# 12_WIFI_Module.net
KiCad netlist of a schematic drawn in Altium Designer
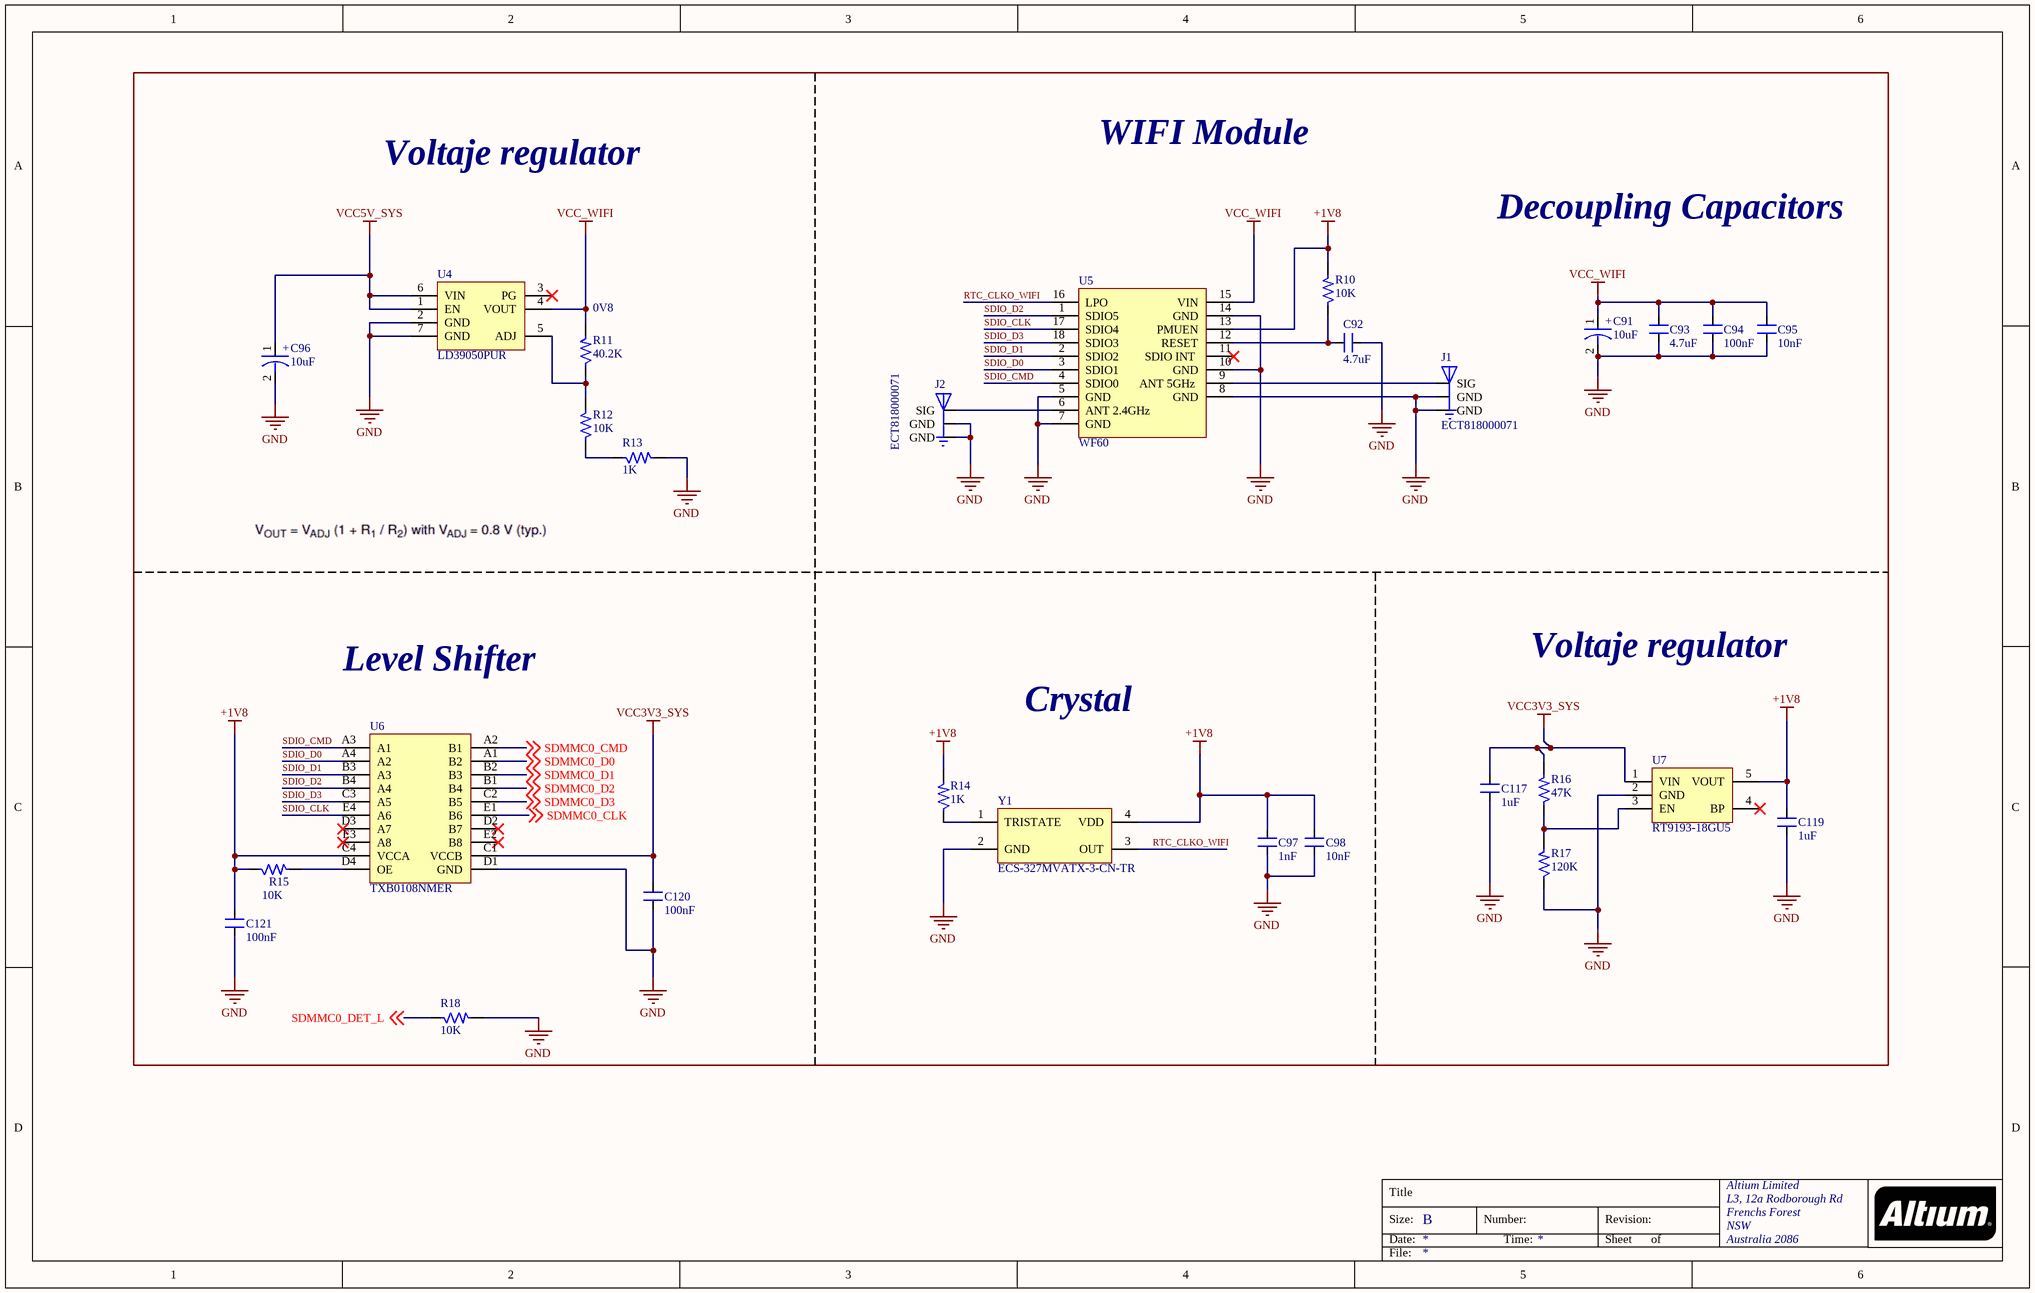
[diagram p0: [12] WIFI_Module.SchDoc]

(export (version "E")
  (design (tool "Eeschema 10.0.6"))
  (components
    (comp (ref "C91")
      (value "10uF")
      (footprint "CAP-T_1206")
      (description "10µF Molded Tantalum Capacitors 16V 1206 (3216 Metric) 3Ohm")
      (fields
        (field (name "MANUFACTURER") "AVX Corporation")
        (field (name "MANUFACTURER PART NUMBER") "TAJA106K016SNJ")
      )
      (libsource (lib "EsteemPCB_SOM_Course_intlib") (part "CAP-P_10uF-16V-10%-1206"))
    )
    (comp (ref "C92")
      (value "4.7uF")
      (footprint "CAP_0201")
      (description "4.7µF ±20% 6.3V Ceramic Capacitor X5R 0201 (0603 Metric)")
      (fields
        (field (name "MANUFACTURER") "Murata Electronics")
        (field (name "MANUFACTURER PART NUMBER") "GRM035R60J475ME15D")
      )
      (libsource (lib "EsteemPCB_SOM_Course_intlib") (part "CAP_4.7uF-6.3V-20%-0201"))
    )
    (comp (ref "C93")
      (value "4.7uF")
      (footprint "CAP_0402")
      (description "4.7µF ±10% 10V Ceramic Capacitor X5R 0402 (1005 Metric)")
      (fields
        (field (name "MANUFACTURER") "Samsung Electro-Mechanics")
        (field (name "MANUFACTURER PART NUMBER") "CL05A475KP5NRNC")
      )
      (libsource (lib "EsteemPCB_SOM_Course_intlib") (part "CAP_4.7uF-10V-10%-0402"))
    )
    (comp (ref "C94")
      (value "100nF")
      (footprint "CAP_0402")
      (description "0.1µF ±10% 25V Ceramic Capacitor X7R 0402 (1005 Metric)")
      (fields
        (field (name "MANUFACTURER") "Walsin Technology Corporation")
        (field (name "MANUFACTURER PART NUMBER") "0402B104K250CT")
      )
      (libsource (lib "EsteemPCB_SOM_Course_intlib") (part "CAP_100nF-25V-10%-0402"))
    )
    (comp (ref "C95")
      (value "10nF")
      (footprint "CAP_0402")
      (description "10000pF ±10% 10V Ceramic Capacitor X7R 0402 (1005 Metric)")
      (fields
        (field (name "MANUFACTURER") "AVX Corporation")
        (field (name "MANUFACTURER PART NUMBER") "0402ZC103KAT2A")
      )
      (libsource (lib "EsteemPCB_SOM_Course_intlib") (part "CAP_10nF-10V-10%-0402"))
    )
    (comp (ref "C96")
      (value "10uF")
      (footprint "CAP-T_1206")
      (description "10µF Molded Tantalum Capacitors 16V 1206 (3216 Metric) 3Ohm")
      (fields
        (field (name "MANUFACTURER") "AVX Corporation")
        (field (name "MANUFACTURER PART NUMBER") "TAJA106K016SNJ")
      )
      (libsource (lib "EsteemPCB_SOM_Course_intlib") (part "CAP-P_10uF-16V-10%-1206"))
    )
    (comp (ref "C97")
      (value "1nF")
      (footprint "CAP_0402")
      (description "1000pF ±10% 10V Ceramic Capacitor X7R 0402 (1005 Metric)")
      (fields
        (field (name "MANUFACTURER") "KEMET")
        (field (name "MANUFACTURER PART NUMBER") "C0402C102K8RACTU")
      )
      (libsource (lib "EsteemPCB_SOM_Course_intlib") (part "CAP_1nF-10V-10%-0402"))
    )
    (comp (ref "C98")
      (value "10nF")
      (footprint "CAP_0402")
      (description "10000pF ±10% 10V Ceramic Capacitor X7R 0402 (1005 Metric)")
      (fields
        (field (name "MANUFACTURER") "AVX Corporation")
        (field (name "MANUFACTURER PART NUMBER") "0402ZC103KAT2A")
      )
      (libsource (lib "EsteemPCB_SOM_Course_intlib") (part "CAP_10nF-10V-10%-0402"))
    )
    (comp (ref "C117")
      (value "1uF")
      (footprint "CAP_0201")
      (description "1µF ±20% 16V Ceramic Capacitor X5R 0201 (0603 Metric)")
      (fields
        (field (name "MANUFACTURER") "Samsung Electro-Mechanics")
        (field (name "MANUFACTURER PART NUMBER") "CL03A105MO3NRNH")
      )
      (libsource (lib "EsteemPCB_SOM_Course_intlib") (part "CAP_1uF-16V-10%-0201"))
    )
    (comp (ref "C119")
      (value "1uF")
      (footprint "CAP_0201")
      (description "1µF ±20% 16V Ceramic Capacitor X5R 0201 (0603 Metric)")
      (fields
        (field (name "MANUFACTURER") "Samsung Electro-Mechanics")
        (field (name "MANUFACTURER PART NUMBER") "CL03A105MO3NRNH")
      )
      (libsource (lib "EsteemPCB_SOM_Course_intlib") (part "CAP_1uF-16V-10%-0201"))
    )
    (comp (ref "C120")
      (value "100nF")
      (footprint "CAP_0201")
      (description "0.1µF ±10% 25V Ceramic Capacitor X5R 0201 (0603 Metric)")
      (fields
        (field (name "MANUFACTURER") "TDK Corporation")
        (field (name "MANUFACTURER PART NUMBER") "C0603X5R1E104K030BB")
      )
      (libsource (lib "EsteemPCB_SOM_Course_intlib") (part "CAP_100nF-25V-10%-0201"))
    )
    (comp (ref "C121")
      (value "100nF")
      (footprint "CAP_0201")
      (description "0.1µF ±10% 25V Ceramic Capacitor X5R 0201 (0603 Metric)")
      (fields
        (field (name "MANUFACTURER") "TDK Corporation")
        (field (name "MANUFACTURER PART NUMBER") "C0603X5R1E104K030BB")
      )
      (libsource (lib "EsteemPCB_SOM_Course_intlib") (part "CAP_100nF-25V-10%-0201"))
    )
    (comp (ref "J1")
      (value "ECT818000071")
      (footprint "CON3_UFL_116_SMD_ST")
      (description "SMD RF Connectors/Coaxial Connectors RoHS")
      (fields (field (name "MANUFACTURER") "ECT"))
      (libsource (lib "EsteemPCB_SOM_Course_intlib") (part "CON-PLG_3X1-ECT818000071-ST-SMD"))
    )
    (comp (ref "J2")
      (value "ECT818000071")
      (footprint "CON3_UFL_116_SMD_ST")
      (description "SMD RF Connectors/Coaxial Connectors RoHS")
      (fields (field (name "MANUFACTURER") "ECT"))
      (libsource (lib "EsteemPCB_SOM_Course_intlib") (part "CON-PLG_3X1-ECT818000071-ST-SMD"))
    )
    (comp (ref "R10")
      (value "10K")
      (footprint "RES_0201")
      (description "10 kOhms ±1% 0.05W, 1/20W Chip Resistor 0201 (0603 Metric) Thick Film")
      (fields
        (field (name "MANUFACTURER") "Stackpole Electronics Inc")
        (field (name "MANUFACTURER PART NUMBER") "RMCF0201FT10K0")
      )
      (libsource (lib "EsteemPCB_SOM_Course_intlib") (part "RES_10K-0.05W-1%-0201"))
    )
    (comp (ref "R11")
      (value "40.2K")
      (footprint "RES_0201")
      (fields
        (field (name "MANUFACTURER") "Yageo")
        (field (name "MANUFACTURER PART NUMBER") "AC0201FR-0740K2L")
      )
      (libsource (lib "EsteemPCB_SOM_Course_intlib") (part "RES_40.2K-0.05W-1%-0201"))
    )
    (comp (ref "R12")
      (value "10K")
      (footprint "RES_0201")
      (description "10 kOhms ±1% 0.05W, 1/20W Chip Resistor 0201 (0603 Metric) Thick Film")
      (fields
        (field (name "MANUFACTURER") "Stackpole Electronics Inc")
        (field (name "MANUFACTURER PART NUMBER") "RMCF0201FT10K0")
      )
      (libsource (lib "EsteemPCB_SOM_Course_intlib") (part "RES_10K-0.05W-1%-0201"))
    )
    (comp (ref "R13")
      (value "1K")
      (footprint "RES_0402")
      (description "1 kOhms ±1% 0.1W, 1/10W Chip Resistor 0402 (1005 Metric) Anti-Sulfur Thin Film")
      (fields
        (field (name "MANUFACTURER") "Vishay Beyschlag/Draloric/BC Components")
        (field (name "MANUFACTURER PART NUMBER") "MCS04020C1001FE000")
      )
      (libsource (lib "EsteemPCB_SOM_Course_intlib") (part "RES_1K-0.1W-1%-0402"))
    )
    (comp (ref "R14")
      (value "1K")
      (footprint "RES_0201")
      (description "10 kOhms ±1% 0.05W, 1/20W Chip Resistor 0201 (0603 Metric) Thick Film")
      (fields
        (field (name "MANUFACTURER") "Stackpole Electronics Inc")
        (field (name "MANUFACTURER PART NUMBER") "RMCF0201FT10K0")
      )
      (libsource (lib "EsteemPCB_SOM_Course_intlib") (part "RES_10K-0.05W-1%-0201"))
    )
    (comp (ref "R15")
      (value "10K")
      (footprint "RES_0201")
      (description "10 kOhms ±1% 0.05W, 1/20W Chip Resistor 0201 (0603 Metric) Thick Film")
      (fields
        (field (name "MANUFACTURER") "Stackpole Electronics Inc")
        (field (name "MANUFACTURER PART NUMBER") "RMCF0201FT10K0")
      )
      (libsource (lib "EsteemPCB_SOM_Course_intlib") (part "RES_10K-0.05W-1%-0201"))
    )
    (comp (ref "R16")
      (value "47K")
      (footprint "RES_0402")
      (description "47 kOhms ±1% 0.1W, 1/10W Chip Resistor 0402 (1005 Metric) Automotive AEC-Q200 Thick Film")
      (fields
        (field (name "MANUFACTURER") "Panasonic Electronic Components")
        (field (name "MANUFACTURER PART NUMBER") "ERJ-2RKF4702X")
      )
      (libsource (lib "EsteemPCB_SOM_Course_intlib") (part "RES_47K-0.1W-1%-0402"))
    )
    (comp (ref "R17")
      (value "120K")
      (footprint "RES_0402")
      (description "120 kOhms ±1% 0.1W, 1/10W Chip Resistor 0402 (1005 Metric) Anti-Sulfur Thin Film")
      (fields
        (field (name "MANUFACTURER") "Vishay Beyschlag/Draloric/BC Components")
        (field (name "MANUFACTURER PART NUMBER") "MCS04020C1203FE000")
      )
      (libsource (lib "EsteemPCB_SOM_Course_intlib") (part "RES_120K-0.1W-1%-0402"))
    )
    (comp (ref "R18")
      (value "10K")
      (footprint "RES_0201")
      (description "10 kOhms ±1% 0.05W, 1/20W Chip Resistor 0201 (0603 Metric) Thick Film")
      (fields
        (field (name "MANUFACTURER") "Stackpole Electronics Inc")
        (field (name "MANUFACTURER PART NUMBER") "RMCF0201FT10K0")
      )
      (libsource (lib "EsteemPCB_SOM_Course_intlib") (part "RES_10K-0.05W-1%-0201"))
    )
    (comp (ref "U4")
      (value "LD39050PUR")
      (footprint "DFN-6_37.4_165_33X15_SMD")
      (description "Adjustable 5.5V 0.8V 500mA DFN-6 Linear Voltage Regulators RoHS")
      (fields (field (name "MANUFACTURER") "STMicroelectronics"))
      (libsource (lib "EsteemPCB_SOM_Course_intlib") (part "REG_5.5V-0~5.1V-0.5A-2.55W-DFN-6"))
    )
    (comp (ref "U5")
      (value "WF60")
      (footprint "MOD_WF60")
      (description "Amp’ed RF Tech presents the WF60 WiFi dual\r\nband module: 802.11abgn.")
      (fields (field (name "MANUFACTURER") "Amp’ed"))
      (libsource (lib "EsteemPCB_SOM_Course_intlib") (part "MOD_WF60-SMD"))
    )
    (comp (ref "U6")
      (value "TXB0108NMER")
      (footprint "NFBGA_31.4_125.9X102.36")
      (fields (field (name "MANUFACTURER") "Texas Instruments"))
      (libsource (lib "EsteemPCB_SOM_Course_intlib") (part "IC_TXB0108NMER"))
    )
    (comp (ref "U7")
      (value "RT9193-18GU5")
      (footprint "SC70-5")
      (description "Linear Voltage Regulator IC 1 Output 300mA SC-70-5")
      (fields (field (name "MANUFACTURER") "Richtek USA Inc."))
      (libsource (lib "EsteemPCB_SOM_Course_intlib") (part "REG_1.8V-300mA-5.5V-SC70-5"))
    )
    (comp (ref "Y1")
      (value "ECS-327MVATX-3-CN-TR")
      (footprint "XTAL_57_35X31_SMD")
      (description "32.768kHz XO (Standard) CMOS Oscillator 1.6V ~ 3.6V Enable/Disable 4-SMD, No Lead")
      (fields (field (name "MANUFACTURER") "ECS INC"))
      (libsource (lib "EsteemPCB_SOM_Course_intlib") (part "XTAL_ECS-327MVATX-2-CN-TR"))
    )
  )
  (nets
    (net (code "1") (name "+1V8") (class "Default")
      (node (ref "C119") (pin "2") (pinfunction "2_2") (pintype "passive"))
      (node (ref "C121") (pin "2") (pinfunction "2_2") (pintype "passive"))
      (node (ref "C97") (pin "2") (pinfunction "2_2") (pintype "passive"))
      (node (ref "C98") (pin "2") (pinfunction "2_2") (pintype "passive"))
      (node (ref "R10") (pin "2") (pinfunction "2_2") (pintype "passive"))
      (node (ref "R14") (pin "2") (pinfunction "2_2") (pintype "passive"))
      (node (ref "R15") (pin "1") (pinfunction "1_1") (pintype "passive"))
      (node (ref "U5") (pin "13") (pinfunction "PMUEN_13") (pintype "passive"))
      (node (ref "U6") (pin "C4") (pinfunction "VCCA_C4") (pintype "passive"))
      (node (ref "U7") (pin "5") (pinfunction "VOUT_5") (pintype "passive"))
      (node (ref "Y1") (pin "4") (pinfunction "VDD_4") (pintype "passive"))
    )
    (net (code "2") (name "/RTC_CLKO_WIFI") (class "Default")
      (node (ref "U5") (pin "16") (pinfunction "LPO_16") (pintype "passive"))
      (node (ref "Y1") (pin "3") (pinfunction "OUT_3") (pintype "passive"))
    )
    (net (code "3") (name "/SDIO_CLK") (class "Default")
      (node (ref "U5") (pin "17") (pinfunction "SDIO4_17") (pintype "passive"))
      (node (ref "U6") (pin "E4") (pinfunction "A6_E4") (pintype "passive"))
    )
    (net (code "4") (name "/SDIO_CMD") (class "Default")
      (node (ref "U5") (pin "4") (pinfunction "SDIO0_4") (pintype "passive"))
      (node (ref "U6") (pin "A3") (pinfunction "A1_A3") (pintype "passive"))
    )
    (net (code "5") (name "/SDIO_D0") (class "Default")
      (node (ref "U5") (pin "3") (pinfunction "SDIO1_3") (pintype "passive"))
      (node (ref "U6") (pin "A4") (pinfunction "A2_A4") (pintype "passive"))
    )
    (net (code "6") (name "/SDIO_D1") (class "Default")
      (node (ref "U5") (pin "2") (pinfunction "SDIO2_2") (pintype "passive"))
      (node (ref "U6") (pin "B3") (pinfunction "A3_B3") (pintype "passive"))
    )
    (net (code "7") (name "/SDIO_D2") (class "Default")
      (node (ref "U5") (pin "1") (pinfunction "SDIO5_1") (pintype "passive"))
      (node (ref "U6") (pin "B4") (pinfunction "A4_B4") (pintype "passive"))
    )
    (net (code "8") (name "/SDIO_D3") (class "Default")
      (node (ref "U5") (pin "18") (pinfunction "SDIO3_18") (pintype "passive"))
      (node (ref "U6") (pin "C3") (pinfunction "A5_C3") (pintype "passive"))
    )
    (net (code "9") (name "GND") (class "Default")
      (node (ref "C117") (pin "1") (pinfunction "1_1") (pintype "passive"))
      (node (ref "C119") (pin "1") (pinfunction "1_1") (pintype "passive"))
      (node (ref "C120") (pin "1") (pinfunction "1_1") (pintype "passive"))
      (node (ref "C121") (pin "1") (pinfunction "1_1") (pintype "passive"))
      (node (ref "C91") (pin "2") (pinfunction "2_2") (pintype "passive"))
      (node (ref "C92") (pin "2") (pinfunction "2_2") (pintype "passive"))
      (node (ref "C93") (pin "1") (pinfunction "1_1") (pintype "passive"))
      (node (ref "C94") (pin "1") (pinfunction "1_1") (pintype "passive"))
      (node (ref "C95") (pin "1") (pinfunction "1_1") (pintype "passive"))
      (node (ref "C96") (pin "2") (pinfunction "2_2") (pintype "passive"))
      (node (ref "C97") (pin "1") (pinfunction "1_1") (pintype "passive"))
      (node (ref "C98") (pin "1") (pinfunction "1_1") (pintype "passive"))
      (node (ref "J1") (pin "1") (pinfunction "GND_1") (pintype "passive"))
      (node (ref "J1") (pin "3") (pinfunction "GND_3") (pintype "passive"))
      (node (ref "J2") (pin "1") (pinfunction "GND_1") (pintype "passive"))
      (node (ref "J2") (pin "3") (pinfunction "GND_3") (pintype "passive"))
      (node (ref "R13") (pin "2") (pinfunction "2_2") (pintype "passive"))
      (node (ref "R17") (pin "1") (pinfunction "1_1") (pintype "passive"))
      (node (ref "R18") (pin "2") (pinfunction "2_2") (pintype "passive"))
      (node (ref "U4") (pin "2") (pinfunction "GND_2") (pintype "passive"))
      (node (ref "U4") (pin "7") (pinfunction "GND_7") (pintype "passive"))
      (node (ref "U5") (pin "10") (pinfunction "GND_10") (pintype "passive"))
      (node (ref "U5") (pin "14") (pinfunction "GND_14") (pintype "passive"))
      (node (ref "U5") (pin "5") (pinfunction "GND_5") (pintype "passive"))
      (node (ref "U5") (pin "7") (pinfunction "GND_7") (pintype "passive"))
      (node (ref "U5") (pin "8") (pinfunction "GND_8") (pintype "passive"))
      (node (ref "U6") (pin "D1") (pinfunction "GND_D1") (pintype "passive"))
      (node (ref "U7") (pin "2") (pinfunction "GND_2") (pintype "passive"))
      (node (ref "Y1") (pin "2") (pinfunction "GND_2") (pintype "passive"))
    )
    (net (code "10") (name "Net-(J1-SIG)") (class "Default")
      (node (ref "J1") (pin "2") (pinfunction "SIG_2") (pintype "passive"))
      (node (ref "U5") (pin "9") (pinfunction "ANT_5GHz_9") (pintype "passive"))
    )
    (net (code "11") (name "Net-(J2-SIG)") (class "Default")
      (node (ref "J2") (pin "2") (pinfunction "SIG_2") (pintype "passive"))
      (node (ref "U5") (pin "6") (pinfunction "ANT_2.4GHz_6") (pintype "passive"))
    )
    (net (code "12") (name "Net-(R12-Pad1)") (class "Default")
      (node (ref "R12") (pin "1") (pinfunction "1_1") (pintype "passive"))
      (node (ref "R13") (pin "1") (pinfunction "1_1") (pintype "passive"))
    )
    (net (code "13") (name "Net-(U4-ADJ)") (class "Default")
      (node (ref "R11") (pin "1") (pinfunction "1_1") (pintype "passive"))
      (node (ref "R12") (pin "2") (pinfunction "2_2") (pintype "passive"))
      (node (ref "U4") (pin "5") (pinfunction "ADJ_5") (pintype "passive"))
    )
    (net (code "14") (name "Net-(U5-RESET)") (class "Default")
      (node (ref "C92") (pin "1") (pinfunction "1_1") (pintype "passive"))
      (node (ref "R10") (pin "1") (pinfunction "1_1") (pintype "passive"))
      (node (ref "U5") (pin "12") (pinfunction "RESET_12") (pintype "passive"))
    )
    (net (code "15") (name "Net-(U6-OE)") (class "Default")
      (node (ref "R15") (pin "2") (pinfunction "2_2") (pintype "passive"))
      (node (ref "U6") (pin "D4") (pinfunction "OE_D4") (pintype "passive"))
    )
    (net (code "16") (name "Net-(U7-EN)") (class "Default")
      (node (ref "R16") (pin "1") (pinfunction "1_1") (pintype "passive"))
      (node (ref "R17") (pin "2") (pinfunction "2_2") (pintype "passive"))
      (node (ref "U7") (pin "3") (pinfunction "EN_3") (pintype "passive"))
    )
    (net (code "17") (name "Net-(Y1-TRISTATE)") (class "Default")
      (node (ref "R14") (pin "1") (pinfunction "1_1") (pintype "passive"))
      (node (ref "Y1") (pin "1") (pinfunction "TRISTATE_1") (pintype "passive"))
    )
    (net (code "18") (name "SDMMC0_CLK") (class "Default")
      (node (ref "U6") (pin "E1") (pinfunction "B6_E1") (pintype "passive"))
    )
    (net (code "19") (name "SDMMC0_CMD") (class "Default")
      (node (ref "U6") (pin "A2") (pinfunction "B1_A2") (pintype "passive"))
    )
    (net (code "20") (name "SDMMC0_D0") (class "Default")
      (node (ref "U6") (pin "A1") (pinfunction "B2_A1") (pintype "passive"))
    )
    (net (code "21") (name "SDMMC0_D1") (class "Default")
      (node (ref "U6") (pin "B2") (pinfunction "B3_B2") (pintype "passive"))
    )
    (net (code "22") (name "SDMMC0_D2") (class "Default")
      (node (ref "U6") (pin "B1") (pinfunction "B4_B1") (pintype "passive"))
    )
    (net (code "23") (name "SDMMC0_D3") (class "Default")
      (node (ref "U6") (pin "C2") (pinfunction "B5_C2") (pintype "passive"))
    )
    (net (code "24") (name "SDMMC0_DET_L") (class "Default")
      (node (ref "R18") (pin "1") (pinfunction "1_1") (pintype "passive"))
    )
    (net (code "25") (name "VCC3V3_SYS") (class "Default")
      (node (ref "C117") (pin "2") (pinfunction "2_2") (pintype "passive"))
      (node (ref "C120") (pin "2") (pinfunction "2_2") (pintype "passive"))
      (node (ref "R16") (pin "2") (pinfunction "2_2") (pintype "passive"))
      (node (ref "U6") (pin "C1") (pinfunction "VCCB_C1") (pintype "passive"))
      (node (ref "U7") (pin "1") (pinfunction "VIN_1") (pintype "passive"))
    )
    (net (code "26") (name "VCC5V_SYS") (class "Default")
      (node (ref "C96") (pin "1") (pinfunction "1_1") (pintype "passive"))
      (node (ref "U4") (pin "1") (pinfunction "EN_1") (pintype "passive"))
      (node (ref "U4") (pin "6") (pinfunction "VIN_6") (pintype "passive"))
    )
    (net (code "27") (name "VCC_WIFI") (class "Default")
      (node (ref "C91") (pin "1") (pinfunction "1_1") (pintype "passive"))
      (node (ref "C93") (pin "2") (pinfunction "2_2") (pintype "passive"))
      (node (ref "C94") (pin "2") (pinfunction "2_2") (pintype "passive"))
      (node (ref "C95") (pin "2") (pinfunction "2_2") (pintype "passive"))
      (node (ref "R11") (pin "2") (pinfunction "2_2") (pintype "passive"))
      (node (ref "U4") (pin "4") (pinfunction "VOUT_4") (pintype "passive"))
      (node (ref "U5") (pin "15") (pinfunction "VIN_15") (pintype "passive"))
    )
    (net (code "28") (name "unconnected-(U4-PG-Pad3)") (class "Default")
      (node (ref "U4") (pin "3") (pinfunction "PG_3") (pintype "passive+no_connect"))
    )
    (net (code "29") (name "unconnected-(U5-SDIO_INT-Pad11)") (class "Default")
      (node (ref "U5") (pin "11") (pinfunction "SDIO_INT_11") (pintype "passive+no_connect"))
    )
    (net (code "30") (name "unconnected-(U6-A7-PadD3)") (class "Default")
      (node (ref "U6") (pin "D3") (pinfunction "A7_D3") (pintype "passive+no_connect"))
    )
    (net (code "31") (name "unconnected-(U6-A8-PadE3)") (class "Default")
      (node (ref "U6") (pin "E3") (pinfunction "A8_E3") (pintype "passive+no_connect"))
    )
    (net (code "32") (name "unconnected-(U6-B7-PadD2)") (class "Default")
      (node (ref "U6") (pin "D2") (pinfunction "B7_D2") (pintype "passive+no_connect"))
    )
    (net (code "33") (name "unconnected-(U6-B8-PadE2)") (class "Default")
      (node (ref "U6") (pin "E2") (pinfunction "B8_E2") (pintype "passive+no_connect"))
    )
    (net (code "34") (name "unconnected-(U7-BP-Pad4)") (class "Default")
      (node (ref "U7") (pin "4") (pinfunction "BP_4") (pintype "passive+no_connect"))
    )
  )
)
